# ChillerLCD.net
KiCad netlist of a schematic drawn in Altium Designer
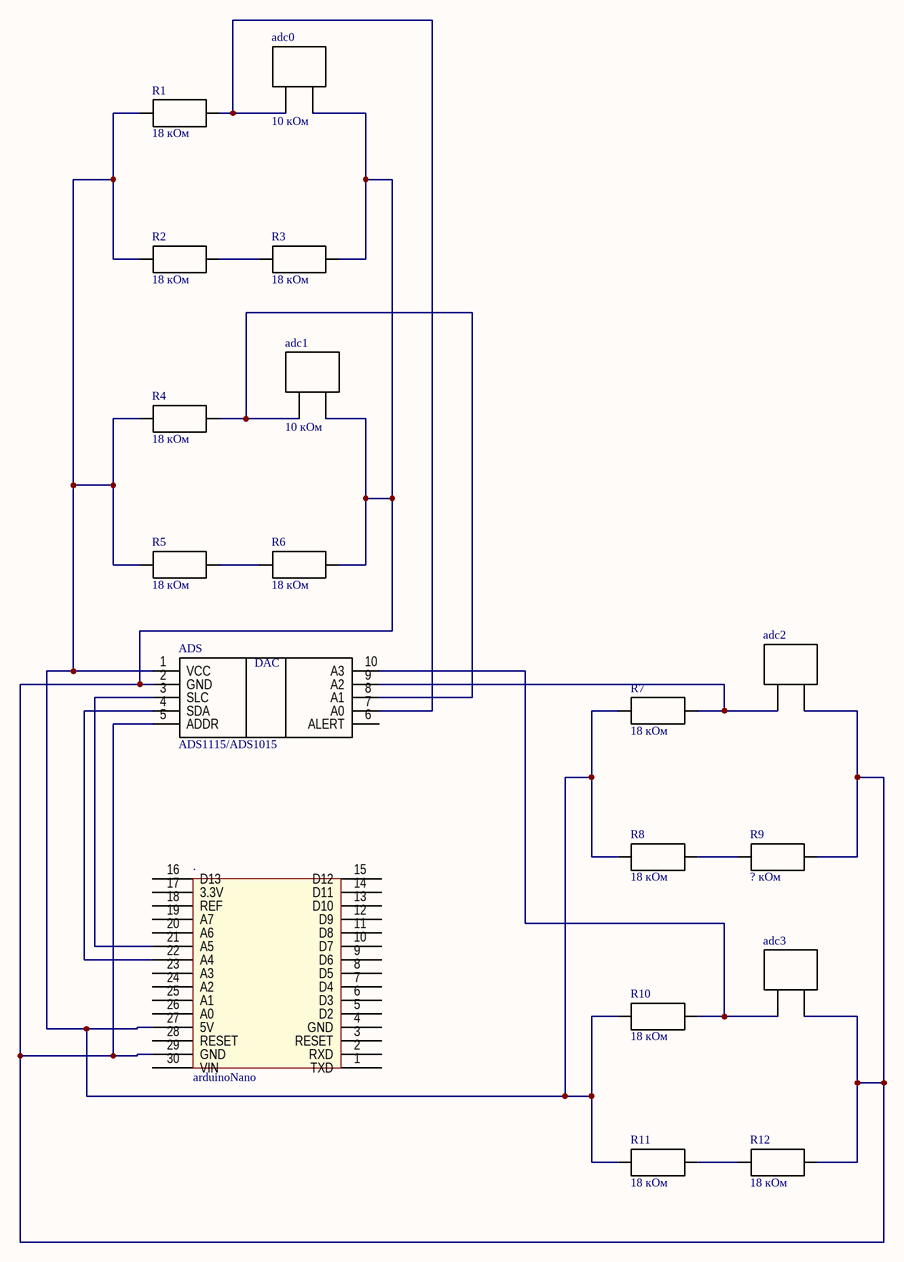
[diagram p0: ChillerLCD.SchDoc]

(export (version "E")
  (design (tool "Eeschema 10.0.6"))
  (components
    (comp (ref ".")
      (value "arduinoNano")
      (footprint "Chiller:Arduino Nano")
      (libsource (lib "Chiller") (part "arduinoNano"))
    )
    (comp (ref "adc0")
      (value "Termoresistor")
      (footprint "Chiller:CWF-2 2.5mm")
      (fields (field (name "ОМ") "10 кОм"))
      (libsource (lib "Chiller") (part "Termoresistor"))
    )
    (comp (ref "adc1")
      (value "Termoresistor")
      (footprint "Chiller:CWF-2 2.5mm")
      (fields (field (name "ОМ") "10 кОм"))
      (libsource (lib "Chiller") (part "Termoresistor"))
    )
    (comp (ref "adc2")
      (value "Pt Resistor")
      (footprint "Chiller:CWF-2 2.5mm")
      (libsource (lib "Chiller") (part "Pt Resistor"))
    )
    (comp (ref "adc3")
      (value "Pt Resistor")
      (footprint "Chiller:CWF-2 2.5mm")
      (libsource (lib "Chiller") (part "Pt Resistor"))
    )
    (comp (ref "ADS")
      (value "ADS1115/ADS1015")
      (footprint "Chiller:ADS1115/ADS1015")
      (libsource (lib "Chiller") (part "ADS1115/ADS1015"))
    )
    (comp (ref "R1")
      (value "Res1206")
      (footprint "Chiller:3216[1206]")
      (fields (field (name "ОМ") "18 кОм"))
      (libsource (lib "Chiller") (part "Res1206"))
    )
    (comp (ref "R2")
      (value "Res1206")
      (footprint "Chiller:3216[1206]")
      (fields (field (name "ОМ") "18 кОм"))
      (libsource (lib "Chiller") (part "Res1206"))
    )
    (comp (ref "R3")
      (value "Res1206")
      (footprint "Chiller:3216[1206]")
      (fields (field (name "ОМ") "18 кОм"))
      (libsource (lib "Chiller") (part "Res1206"))
    )
    (comp (ref "R4")
      (value "Res1206")
      (footprint "Chiller:3216[1206]")
      (fields (field (name "ОМ") "18 кОм"))
      (libsource (lib "Chiller") (part "Res1206"))
    )
    (comp (ref "R5")
      (value "Res1206")
      (footprint "Chiller:3216[1206]")
      (fields (field (name "ОМ") "18 кОм"))
      (libsource (lib "Chiller") (part "Res1206"))
    )
    (comp (ref "R6")
      (value "Res1206")
      (footprint "Chiller:3216[1206]")
      (fields (field (name "ОМ") "18 кОм"))
      (libsource (lib "Chiller") (part "Res1206"))
    )
    (comp (ref "R7")
      (value "Res1206")
      (footprint "Chiller:3216[1206]")
      (fields (field (name "ОМ") "18 кОм"))
      (libsource (lib "Chiller") (part "Res1206"))
    )
    (comp (ref "R8")
      (value "Res1206")
      (footprint "Chiller:3216[1206]")
      (fields (field (name "ОМ") "18 кОм"))
      (libsource (lib "Chiller") (part "Res1206"))
    )
    (comp (ref "R9")
      (value "Res1206")
      (footprint "Chiller:3216[1206]")
      (fields (field (name "ОМ") "? кОм"))
      (libsource (lib "Chiller") (part "Res1206"))
    )
    (comp (ref "R10")
      (value "Res1206")
      (footprint "Chiller:3216[1206]")
      (fields (field (name "ОМ") "18 кОм"))
      (libsource (lib "Chiller") (part "Res1206"))
    )
    (comp (ref "R11")
      (value "Res1206")
      (footprint "Chiller:3216[1206]")
      (fields (field (name "ОМ") "18 кОм"))
      (libsource (lib "Chiller") (part "Res1206"))
    )
    (comp (ref "R12")
      (value "Res1206")
      (footprint "Chiller:3216[1206]")
      (fields (field (name "ОМ") "18 кОм"))
      (libsource (lib "Chiller") (part "Res1206"))
    )
  )
  (nets
    (net (code "1") (name "Net-(.-5V)") (class "Default")
      (node (ref ".") (pin "27") (pinfunction "5V_27") (pintype "passive"))
      (node (ref "ADS") (pin "1") (pinfunction "VCC_1") (pintype "passive"))
      (node (ref "R1") (pin "1") (pinfunction "1_1") (pintype "passive"))
      (node (ref "R10") (pin "1") (pinfunction "1_1") (pintype "passive"))
      (node (ref "R11") (pin "1") (pinfunction "1_1") (pintype "passive"))
      (node (ref "R2") (pin "1") (pinfunction "1_1") (pintype "passive"))
      (node (ref "R4") (pin "1") (pinfunction "1_1") (pintype "passive"))
      (node (ref "R5") (pin "1") (pinfunction "1_1") (pintype "passive"))
      (node (ref "R7") (pin "1") (pinfunction "1_1") (pintype "passive"))
      (node (ref "R8") (pin "1") (pinfunction "1_1") (pintype "passive"))
    )
    (net (code "2") (name "Net-(.-A4)") (class "Default")
      (node (ref ".") (pin "22") (pinfunction "A4_22") (pintype "passive"))
      (node (ref "ADS") (pin "4") (pinfunction "SDA_4") (pintype "passive"))
    )
    (net (code "3") (name "Net-(.-A5)") (class "Default")
      (node (ref ".") (pin "21") (pinfunction "A5_21") (pintype "passive"))
      (node (ref "ADS") (pin "3") (pinfunction "SLC_3") (pintype "passive"))
    )
    (net (code "4") (name "Net-(ADS-A0)") (class "Default")
      (node (ref "ADS") (pin "7") (pinfunction "A0_7") (pintype "passive"))
      (node (ref "R1") (pin "2") (pinfunction "2_2") (pintype "passive"))
      (node (ref "adc0") (pin "1") (pinfunction "1_1") (pintype "passive"))
    )
    (net (code "5") (name "Net-(ADS-A1)") (class "Default")
      (node (ref "ADS") (pin "8") (pinfunction "A1_8") (pintype "passive"))
      (node (ref "R4") (pin "2") (pinfunction "2_2") (pintype "passive"))
      (node (ref "adc1") (pin "1") (pinfunction "1_1") (pintype "passive"))
    )
    (net (code "6") (name "Net-(ADS-A2)") (class "Default")
      (node (ref "ADS") (pin "9") (pinfunction "A2_9") (pintype "passive"))
      (node (ref "R7") (pin "2") (pinfunction "2_2") (pintype "passive"))
      (node (ref "adc2") (pin "1") (pinfunction "1_1") (pintype "passive"))
    )
    (net (code "7") (name "Net-(ADS-A3)") (class "Default")
      (node (ref "ADS") (pin "10") (pinfunction "A3_10") (pintype "passive"))
      (node (ref "R10") (pin "2") (pinfunction "2_2") (pintype "passive"))
      (node (ref "adc3") (pin "1") (pinfunction "1_1") (pintype "passive"))
    )
    (net (code "8") (name "Net-(ADS-ADDR)") (class "Default")
      (node (ref ".") (pin "29") (pinfunction "GND_29") (pintype "passive"))
      (node (ref "ADS") (pin "2") (pinfunction "GND_2") (pintype "passive"))
      (node (ref "ADS") (pin "5") (pinfunction "ADDR_5") (pintype "passive"))
      (node (ref "R12") (pin "2") (pinfunction "2_2") (pintype "passive"))
      (node (ref "R3") (pin "2") (pinfunction "2_2") (pintype "passive"))
      (node (ref "R6") (pin "2") (pinfunction "2_2") (pintype "passive"))
      (node (ref "R9") (pin "2") (pinfunction "2_2") (pintype "passive"))
      (node (ref "adc0") (pin "2") (pinfunction "2_2") (pintype "passive"))
      (node (ref "adc1") (pin "2") (pinfunction "2_2") (pintype "passive"))
      (node (ref "adc2") (pin "2") (pinfunction "2_2") (pintype "passive"))
      (node (ref "adc3") (pin "2") (pinfunction "2_2") (pintype "passive"))
    )
    (net (code "9") (name "Net-(R2-Pad2)") (class "Default")
      (node (ref "R2") (pin "2") (pinfunction "2_2") (pintype "passive"))
      (node (ref "R3") (pin "1") (pinfunction "1_1") (pintype "passive"))
    )
    (net (code "10") (name "Net-(R5-Pad2)") (class "Default")
      (node (ref "R5") (pin "2") (pinfunction "2_2") (pintype "passive"))
      (node (ref "R6") (pin "1") (pinfunction "1_1") (pintype "passive"))
    )
    (net (code "11") (name "Net-(R8-Pad2)") (class "Default")
      (node (ref "R8") (pin "2") (pinfunction "2_2") (pintype "passive"))
      (node (ref "R9") (pin "1") (pinfunction "1_1") (pintype "passive"))
    )
    (net (code "12") (name "Net-(R11-Pad2)") (class "Default")
      (node (ref "R11") (pin "2") (pinfunction "2_2") (pintype "passive"))
      (node (ref "R12") (pin "1") (pinfunction "1_1") (pintype "passive"))
    )
    (net (code "13") (name "unconnected-(.-3.3V-Pad17)") (class "Default")
      (node (ref ".") (pin "17") (pinfunction "3.3V_17") (pintype "passive"))
    )
    (net (code "14") (name "unconnected-(.-A0-Pad26)") (class "Default")
      (node (ref ".") (pin "26") (pinfunction "A0_26") (pintype "passive"))
    )
    (net (code "15") (name "unconnected-(.-A1-Pad25)") (class "Default")
      (node (ref ".") (pin "25") (pinfunction "A1_25") (pintype "passive"))
    )
    (net (code "16") (name "unconnected-(.-A2-Pad24)") (class "Default")
      (node (ref ".") (pin "24") (pinfunction "A2_24") (pintype "passive"))
    )
    (net (code "17") (name "unconnected-(.-A3-Pad23)") (class "Default")
      (node (ref ".") (pin "23") (pinfunction "A3_23") (pintype "passive"))
    )
    (net (code "18") (name "unconnected-(.-A6-Pad20)") (class "Default")
      (node (ref ".") (pin "20") (pinfunction "A6_20") (pintype "passive"))
    )
    (net (code "19") (name "unconnected-(.-A7-Pad19)") (class "Default")
      (node (ref ".") (pin "19") (pinfunction "A7_19") (pintype "passive"))
    )
    (net (code "20") (name "unconnected-(.-D2-Pad5)") (class "Default")
      (node (ref ".") (pin "5") (pinfunction "D2_5") (pintype "passive"))
    )
    (net (code "21") (name "unconnected-(.-D3-Pad6)") (class "Default")
      (node (ref ".") (pin "6") (pinfunction "D3_6") (pintype "passive"))
    )
    (net (code "22") (name "unconnected-(.-D4-Pad7)") (class "Default")
      (node (ref ".") (pin "7") (pinfunction "D4_7") (pintype "passive"))
    )
    (net (code "23") (name "unconnected-(.-D5-Pad8)") (class "Default")
      (node (ref ".") (pin "8") (pinfunction "D5_8") (pintype "passive"))
    )
    (net (code "24") (name "unconnected-(.-D6-Pad9)") (class "Default")
      (node (ref ".") (pin "9") (pinfunction "D6_9") (pintype "passive"))
    )
    (net (code "25") (name "unconnected-(.-D7-Pad10)") (class "Default")
      (node (ref ".") (pin "10") (pinfunction "D7_10") (pintype "passive"))
    )
    (net (code "26") (name "unconnected-(.-D8-Pad11)") (class "Default")
      (node (ref ".") (pin "11") (pinfunction "D8_11") (pintype "passive"))
    )
    (net (code "27") (name "unconnected-(.-D9-Pad12)") (class "Default")
      (node (ref ".") (pin "12") (pinfunction "D9_12") (pintype "passive"))
    )
    (net (code "28") (name "unconnected-(.-D10-Pad13)") (class "Default")
      (node (ref ".") (pin "13") (pinfunction "D10_13") (pintype "passive"))
    )
    (net (code "29") (name "unconnected-(.-D11-Pad14)") (class "Default")
      (node (ref ".") (pin "14") (pinfunction "D11_14") (pintype "passive"))
    )
    (net (code "30") (name "unconnected-(.-D12-Pad15)") (class "Default")
      (node (ref ".") (pin "15") (pinfunction "D12_15") (pintype "passive"))
    )
    (net (code "31") (name "unconnected-(.-D13-Pad16)") (class "Default")
      (node (ref ".") (pin "16") (pinfunction "D13_16") (pintype "passive"))
    )
    (net (code "32") (name "unconnected-(.-GND-Pad4)") (class "Default")
      (node (ref ".") (pin "4") (pinfunction "GND_4") (pintype "passive"))
    )
    (net (code "33") (name "unconnected-(.-REF-Pad18)") (class "Default")
      (node (ref ".") (pin "18") (pinfunction "REF_18") (pintype "passive"))
    )
    (net (code "34") (name "unconnected-(.-RESET-Pad3)") (class "Default")
      (node (ref ".") (pin "3") (pinfunction "RESET_3") (pintype "passive"))
    )
    (net (code "35") (name "unconnected-(.-RESET-Pad28)") (class "Default")
      (node (ref ".") (pin "28") (pinfunction "RESET_28") (pintype "passive"))
    )
    (net (code "36") (name "unconnected-(.-RXD-Pad2)") (class "Default")
      (node (ref ".") (pin "2") (pinfunction "RXD_2") (pintype "passive"))
    )
    (net (code "37") (name "unconnected-(.-TXD-Pad1)") (class "Default")
      (node (ref ".") (pin "1") (pinfunction "TXD_1") (pintype "passive"))
    )
    (net (code "38") (name "unconnected-(.-VIN-Pad30)") (class "Default")
      (node (ref ".") (pin "30") (pinfunction "VIN_30") (pintype "passive"))
    )
    (net (code "39") (name "unconnected-(ADS-ALERT-Pad6)") (class "Default")
      (node (ref "ADS") (pin "6") (pinfunction "ALERT_6") (pintype "passive"))
    )
  )
)
